# V3_Mpu6050.net
KiCad netlist of a schematic drawn in Altium Designer
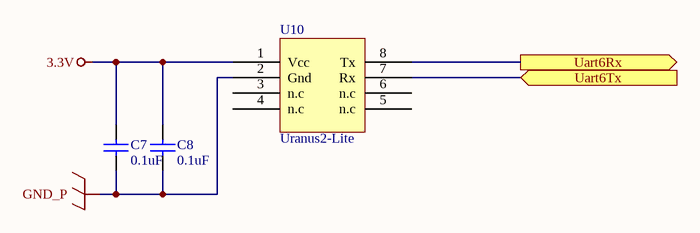
[diagram p0: 海关全向本体电路板V3_Mpu6050模块.SchDoc]

(export (version "E")
  (design (tool "Eeschema 10.0.6"))
  (components
    (comp (ref "C7")
      (value "0.1uF")
      (footprint "C0603-S")
      (description "CAP")
      (fields (field (name "PUBLISHER") "Altium Limited"))
      (libsource (lib "Passive Components Class") (part "CAP"))
    )
    (comp (ref "C8")
      (value "0.1uF")
      (footprint "C0603-S")
      (description "CAP")
      (fields (field (name "PUBLISHER") "Altium Limited"))
      (libsource (lib "Passive Components Class") (part "CAP"))
    )
    (comp (ref "U10")
      (value "Uranus2-Lite")
      (footprint "Uranus2-Lite")
      (libsource (lib "Productor Class") (part "Uranus2-Lite"))
    )
  )
  (nets
    (net (code "1") (name "/Uart6Rx") (class "Default")
      (node (ref "U10") (pin "8") (pinfunction "Tx_8") (pintype "passive"))
    )
    (net (code "2") (name "/Uart6Tx") (class "Default")
      (node (ref "U10") (pin "7") (pinfunction "Rx_7") (pintype "passive"))
    )
    (net (code "3") (name "3.3V") (class "Default")
      (node (ref "C7") (pin "2") (pinfunction "2_2") (pintype "passive"))
      (node (ref "C8") (pin "2") (pinfunction "2_2") (pintype "passive"))
      (node (ref "U10") (pin "1") (pinfunction "Vcc_1") (pintype "passive"))
    )
    (net (code "4") (name "GND_P") (class "Default")
      (node (ref "C7") (pin "1") (pinfunction "1_1") (pintype "passive"))
      (node (ref "C8") (pin "1") (pinfunction "1_1") (pintype "passive"))
      (node (ref "U10") (pin "2") (pinfunction "Gnd_2") (pintype "passive"))
    )
    (net (code "5") (name "unconnected-(U10-n.c-Pad3)") (class "Default")
      (node (ref "U10") (pin "3") (pinfunction "n.c_3") (pintype "passive"))
    )
    (net (code "6") (name "unconnected-(U10-n.c-Pad4)") (class "Default")
      (node (ref "U10") (pin "4") (pinfunction "n.c_4") (pintype "passive"))
    )
    (net (code "7") (name "unconnected-(U10-n.c-Pad5)") (class "Default")
      (node (ref "U10") (pin "5") (pinfunction "n.c_5") (pintype "passive"))
    )
    (net (code "8") (name "unconnected-(U10-n.c-Pad6)") (class "Default")
      (node (ref "U10") (pin "6") (pinfunction "n.c_6") (pintype "passive"))
    )
  )
)
